# Sheet2_datciki.net
KiCad netlist of a schematic drawn in Altium Designer
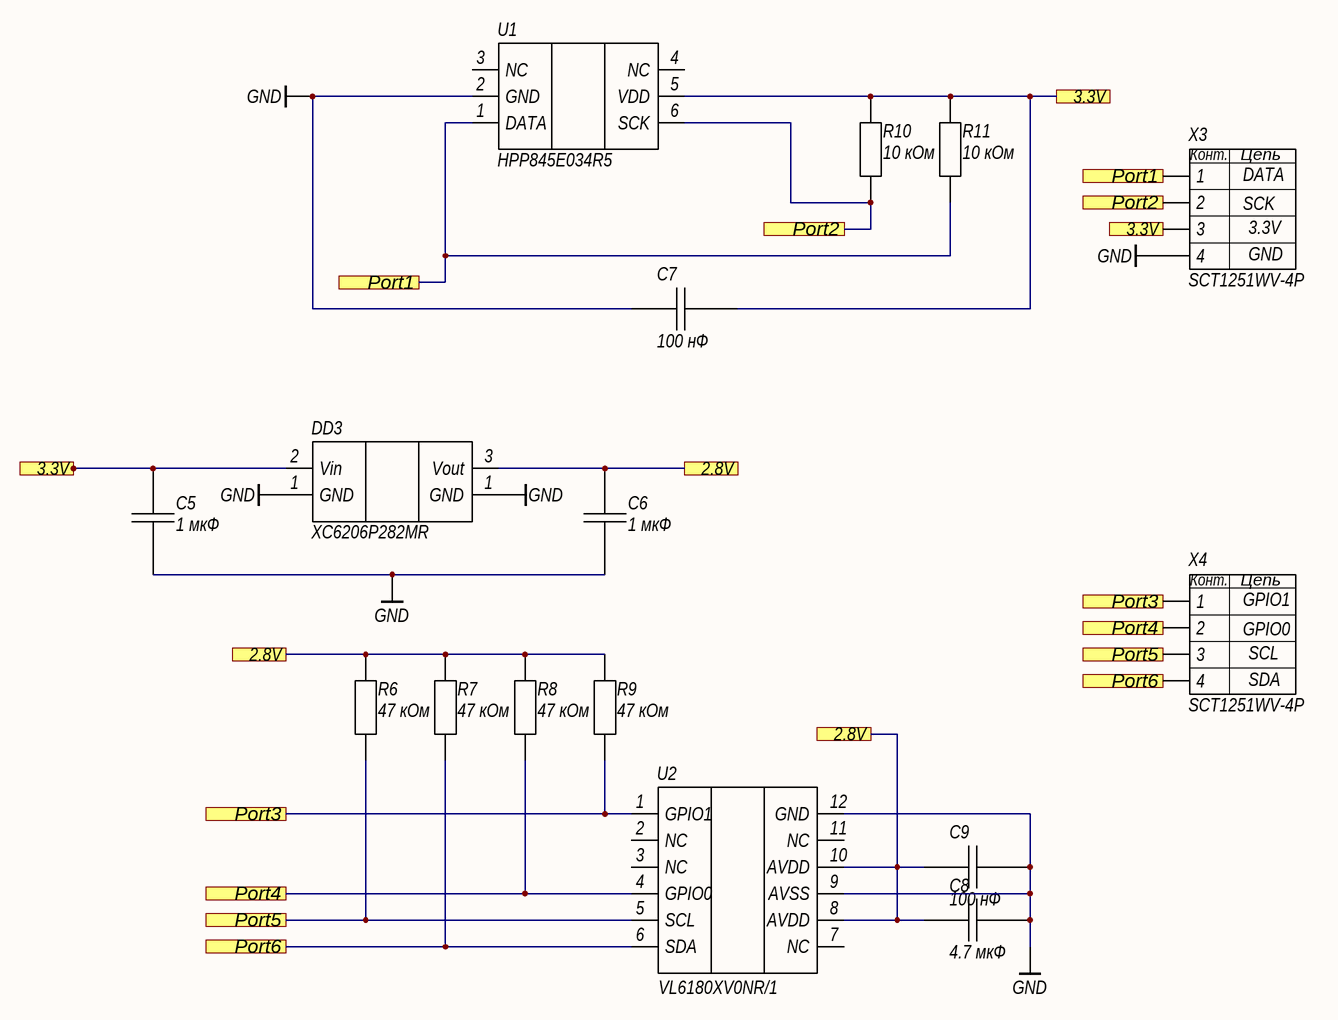
[diagram p0: Sheet2_datciki.SchDoc]

(export (version "E")
  (design (tool "Eeschema 10.0.6"))
  (components
    (comp (ref "C5") (value "1 мкФ") (footprint "CAP_0805") (libsource (lib "Schlib1") (part "Condensator")))
    (comp (ref "C6") (value "1 мкФ") (footprint "CAP_0805") (libsource (lib "Schlib1") (part "Condensator")))
    (comp (ref "C7") (value "100 нФ") (footprint "CAP_0805") (libsource (lib "Schlib1") (part "Condensator")))
    (comp (ref "C8")
      (value "4.7 мкФ")
      (footprint "CAP_0805")
      (libsource (lib "Schlib1") (part "Condensator"))
    )
    (comp (ref "C9") (value "100 нФ") (footprint "CAP_0805") (libsource (lib "Schlib1") (part "Condensator")))
    (comp (ref "DD3")
      (value "XC6206P282MR")
      (footprint "SOT-23-3_STAB_POWER")
      (libsource (lib "Schlib1") (part "Stability_power"))
    )
    (comp (ref "R6") (value "47 кОм") (footprint "RES_0603") (libsource (lib "Schlib1") (part "Rezistor")))
    (comp (ref "R7") (value "47 кОм") (footprint "RES_0603") (libsource (lib "Schlib1") (part "Rezistor")))
    (comp (ref "R8") (value "47 кОм") (footprint "RES_0603") (libsource (lib "Schlib1") (part "Rezistor")))
    (comp (ref "R9") (value "47 кОм") (footprint "RES_0603") (libsource (lib "Schlib1") (part "Rezistor")))
    (comp (ref "R10") (value "10 кОм") (footprint "RES_0603") (libsource (lib "Schlib1") (part "Rezistor")))
    (comp (ref "R11") (value "10 кОм") (footprint "RES_0603") (libsource (lib "Schlib1") (part "Rezistor")))
    (comp (ref "U1")
      (value "HPP845E034R5")
      (footprint "HTU20D(F)")
      (libsource (lib "Schlib1") (part "Datchik_vlaj_temp"))
    )
    (comp (ref "U2")
      (value "VL6180XV0NR/1")
      (footprint "SOP12")
      (libsource (lib "Schlib1") (part "Datchik_osvet"))
    )
    (comp (ref "X3")
      (value "SCT1251WV-4P")
      (footprint "Raziem4(1)_1.25mm")
      (libsource (lib "Schlib1") (part "Raziem_4KONTKTA_1"))
    )
    (comp (ref "X4")
      (value "SCT1251WV-4P")
      (footprint "Raziem4(1)_1.25mm")
      (libsource (lib "Schlib1") (part "Raziem_4KONTKTA"))
    )
  )
  (nets
    (net (code "1") (name "/2.8V") (class "Default")
      (node (ref "C6") (pin "1") (pinfunction "1_1") (pintype "passive"))
      (node (ref "C8") (pin "1") (pinfunction "1_1") (pintype "passive"))
      (node (ref "C9") (pin "1") (pinfunction "1_1") (pintype "passive"))
      (node (ref "DD3") (pin "3") (pinfunction "Vout_3") (pintype "passive"))
      (node (ref "R6") (pin "2") (pinfunction "2_2") (pintype "passive"))
      (node (ref "R7") (pin "2") (pinfunction "2_2") (pintype "passive"))
      (node (ref "R8") (pin "2") (pinfunction "2_2") (pintype "passive"))
      (node (ref "R9") (pin "2") (pinfunction "2_2") (pintype "passive"))
      (node (ref "U2") (pin "10") (pinfunction "AVDD_10") (pintype "passive"))
      (node (ref "U2") (pin "8") (pinfunction "AVDD_8") (pintype "passive"))
    )
    (net (code "2") (name "/3.3V") (class "Default")
      (node (ref "C5") (pin "1") (pinfunction "1_1") (pintype "passive"))
      (node (ref "C7") (pin "2") (pinfunction "2_2") (pintype "passive"))
      (node (ref "DD3") (pin "2") (pinfunction "Vin_2") (pintype "passive"))
      (node (ref "R10") (pin "2") (pinfunction "2_2") (pintype "passive"))
      (node (ref "R11") (pin "2") (pinfunction "2_2") (pintype "passive"))
      (node (ref "U1") (pin "5") (pinfunction "VDD_5") (pintype "passive"))
      (node (ref "X3") (pin "3") (pinfunction "3_3") (pintype "passive"))
    )
    (net (code "3") (name "/Port1") (class "Default")
      (node (ref "R11") (pin "1") (pinfunction "1_1") (pintype "passive"))
      (node (ref "U1") (pin "1") (pinfunction "DATA_1") (pintype "passive"))
      (node (ref "X3") (pin "1") (pinfunction "1_1") (pintype "passive"))
    )
    (net (code "4") (name "/Port2") (class "Default")
      (node (ref "R10") (pin "1") (pinfunction "1_1") (pintype "passive"))
      (node (ref "U1") (pin "6") (pinfunction "SCK_6") (pintype "passive"))
      (node (ref "X3") (pin "2") (pinfunction "2_2") (pintype "passive"))
    )
    (net (code "5") (name "/Port3") (class "Default")
      (node (ref "R9") (pin "1") (pinfunction "1_1") (pintype "passive"))
      (node (ref "U2") (pin "1") (pinfunction "GPIO1_1") (pintype "passive"))
      (node (ref "X4") (pin "1") (pinfunction "1_1") (pintype "passive"))
    )
    (net (code "6") (name "/Port4") (class "Default")
      (node (ref "R8") (pin "1") (pinfunction "1_1") (pintype "passive"))
      (node (ref "U2") (pin "4") (pinfunction "GPIO0_4") (pintype "passive"))
      (node (ref "X4") (pin "2") (pinfunction "2_2") (pintype "passive"))
    )
    (net (code "7") (name "/Port5") (class "Default")
      (node (ref "R6") (pin "1") (pinfunction "1_1") (pintype "passive"))
      (node (ref "U2") (pin "5") (pinfunction "SCL_5") (pintype "passive"))
      (node (ref "X4") (pin "3") (pinfunction "3_3") (pintype "passive"))
    )
    (net (code "8") (name "/Port6") (class "Default")
      (node (ref "R7") (pin "1") (pinfunction "1_1") (pintype "passive"))
      (node (ref "U2") (pin "6") (pinfunction "SDA_6") (pintype "passive"))
      (node (ref "X4") (pin "4") (pinfunction "4_4") (pintype "passive"))
    )
    (net (code "9") (name "GND") (class "Default")
      (node (ref "C5") (pin "2") (pinfunction "2_2") (pintype "passive"))
      (node (ref "C6") (pin "2") (pinfunction "2_2") (pintype "passive"))
      (node (ref "C7") (pin "1") (pinfunction "1_1") (pintype "passive"))
      (node (ref "C8") (pin "2") (pinfunction "2_2") (pintype "passive"))
      (node (ref "C9") (pin "2") (pinfunction "2_2") (pintype "passive"))
      (node (ref "DD3") (pin "1") (pinfunction "GND_1") (pintype "passive"))
      (node (ref "U1") (pin "2") (pinfunction "GND_2") (pintype "passive"))
      (node (ref "U2") (pin "12") (pinfunction "GND_12") (pintype "passive"))
      (node (ref "U2") (pin "9") (pinfunction "AVSS_9") (pintype "passive"))
      (node (ref "X3") (pin "4") (pinfunction "4_4") (pintype "passive"))
    )
    (net (code "10") (name "unconnected-(U1-NC-Pad3)") (class "Default")
      (node (ref "U1") (pin "3") (pinfunction "NC_3") (pintype "passive"))
    )
    (net (code "11") (name "unconnected-(U1-NC-Pad4)") (class "Default")
      (node (ref "U1") (pin "4") (pinfunction "NC_4") (pintype "passive"))
    )
    (net (code "12") (name "unconnected-(U2-NC-Pad2)") (class "Default")
      (node (ref "U2") (pin "2") (pinfunction "NC_2") (pintype "passive"))
    )
    (net (code "13") (name "unconnected-(U2-NC-Pad3)") (class "Default")
      (node (ref "U2") (pin "3") (pinfunction "NC_3") (pintype "passive"))
    )
    (net (code "14") (name "unconnected-(U2-NC-Pad7)") (class "Default")
      (node (ref "U2") (pin "7") (pinfunction "NC_7") (pintype "passive"))
    )
    (net (code "15") (name "unconnected-(U2-NC-Pad11)") (class "Default")
      (node (ref "U2") (pin "11") (pinfunction "NC_11") (pintype "passive"))
    )
  )
)
